# clock_v2.net
KiCad netlist of a schematic drawn in EAGLE
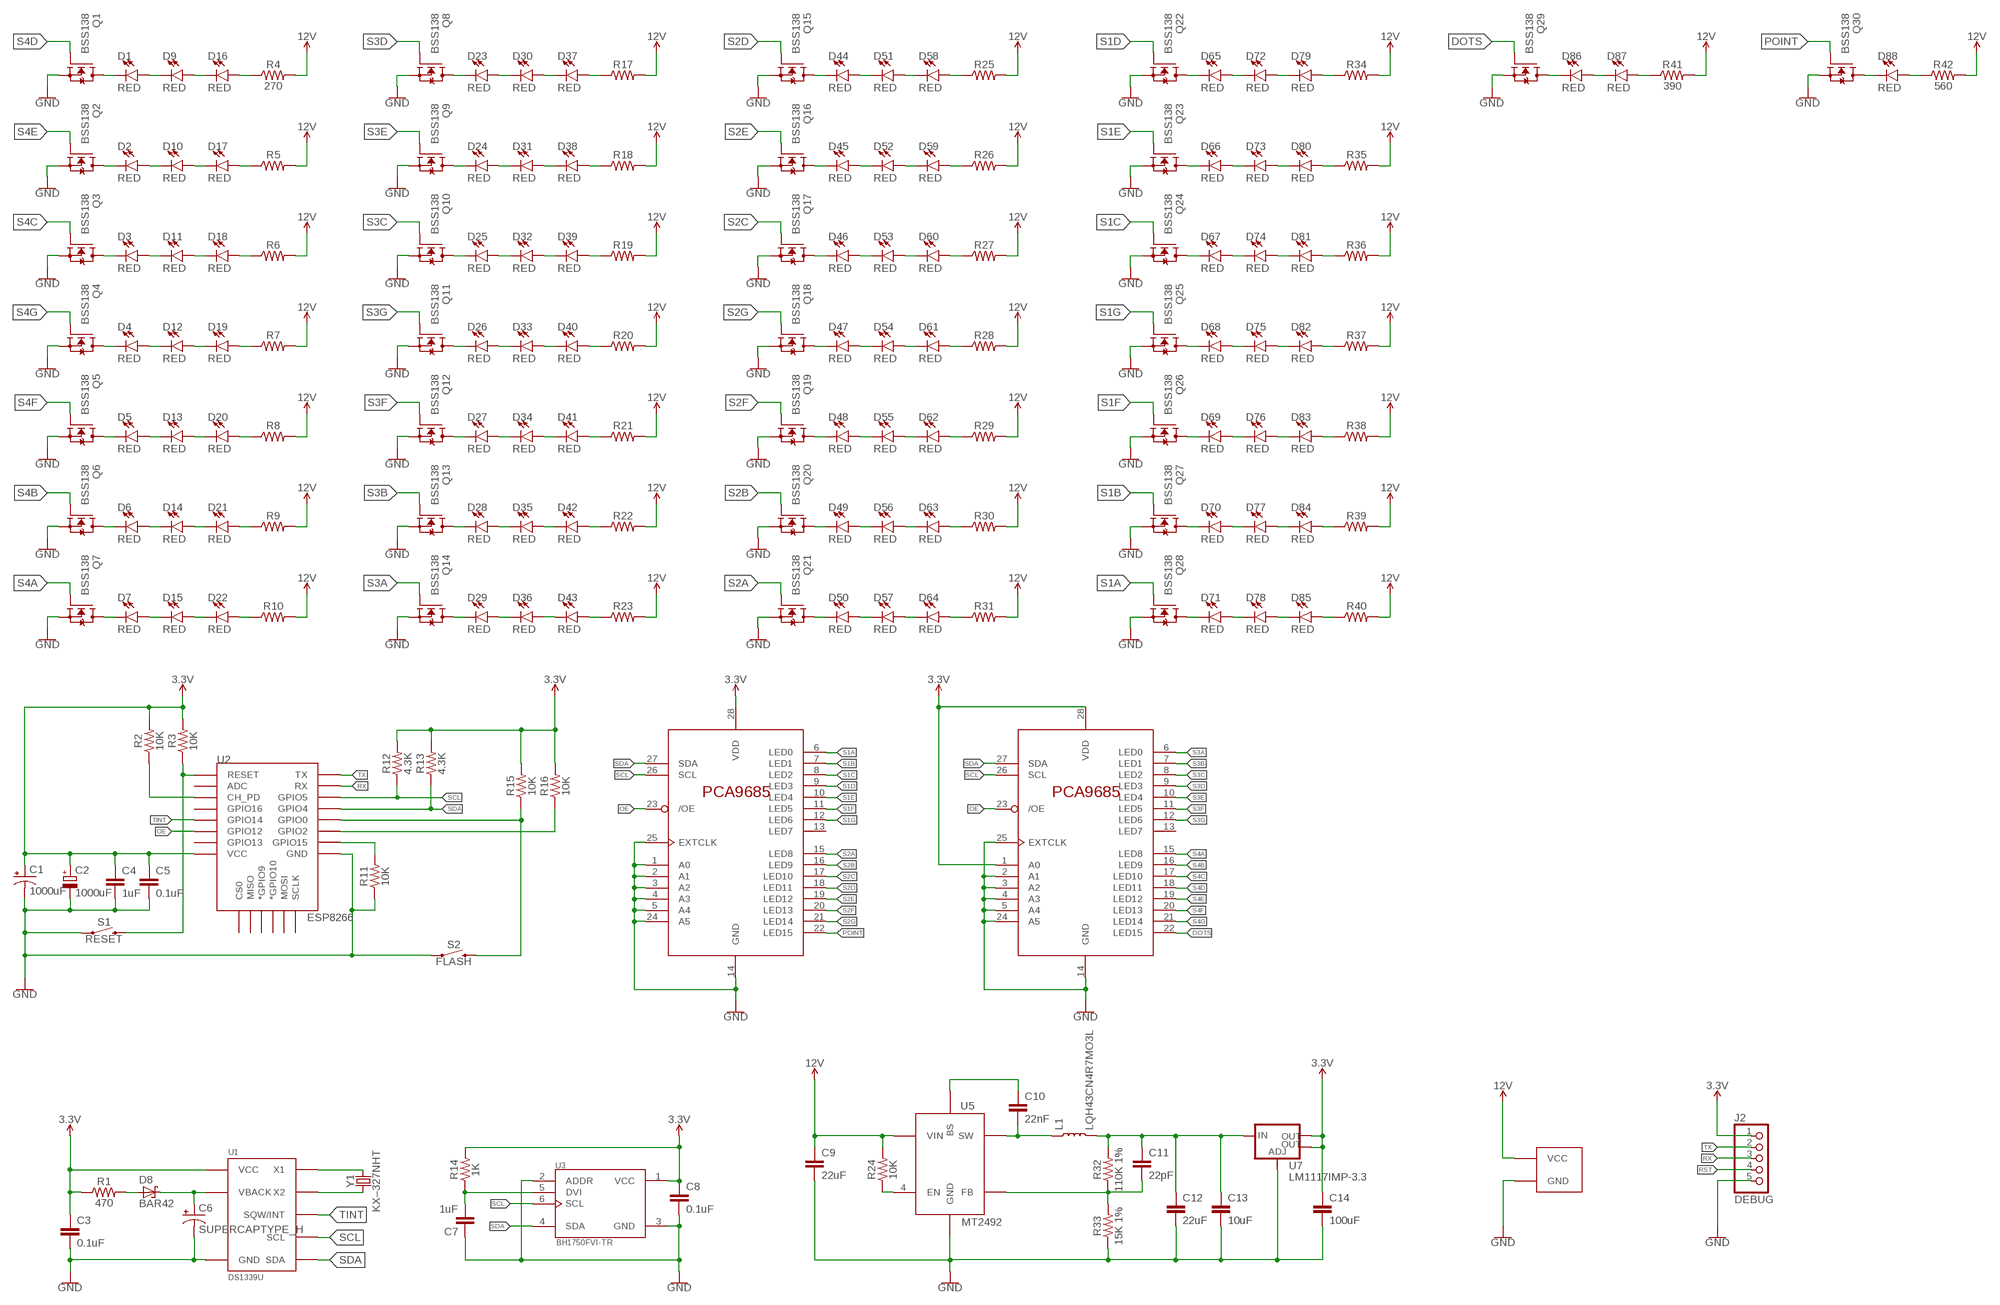
[diagram p0: schematic, sheet 1]

(export (version "E")
  (design (tool "Eeschema 10.0.6"))
  (components
    (comp (ref "C1")
      (value "1000uF")
      (footprint "eagle-import:CAP_8X11.5_P-3.5")
      (libsource (lib "eagle-import") (part "CAP-RADIAL-8MM"))
    )
    (comp (ref "C2")
      (value "1000uF")
      (footprint "eagle-import:D_7343-31R")
      (libsource (lib "eagle-import") (part "CPOL-EUD/7343-31R"))
    )
    (comp (ref "C3")
      (value "0.1uF")
      (footprint "eagle-import:1206")
      (libsource (lib "eagle-import") (part "1.0UF-1206-50V-10%"))
    )
    (comp (ref "C4")
      (value "1uF")
      (footprint "eagle-import:1206")
      (libsource (lib "eagle-import") (part "1.0UF-1206-50V-10%"))
    )
    (comp (ref "C5")
      (value "0.1uF")
      (footprint "eagle-import:1206")
      (libsource (lib "eagle-import") (part "1.0UF-1206-50V-10%"))
    )
    (comp (ref "C6")
      (value "SUPERCAPTYPE_H")
      (footprint "eagle-import:IONISTOR_TYPE_H")
      (libsource (lib "eagle-import") (part "SUPERCAPTYPE_H"))
    )
    (comp (ref "C7")
      (value "1uF")
      (footprint "eagle-import:1206")
      (libsource (lib "eagle-import") (part "1.0UF-1206-50V-10%"))
    )
    (comp (ref "C8")
      (value "0.1uF")
      (footprint "eagle-import:1206")
      (libsource (lib "eagle-import") (part "1.0UF-1206-50V-10%"))
    )
    (comp (ref "C9")
      (value "22uF")
      (footprint "eagle-import:1206")
      (libsource (lib "eagle-import") (part "1.0UF-1206-50V-10%"))
    )
    (comp (ref "C10")
      (value "22nF")
      (footprint "eagle-import:1206")
      (libsource (lib "eagle-import") (part "1.0UF-1206-50V-10%"))
    )
    (comp (ref "C11")
      (value "22pF")
      (footprint "eagle-import:1206")
      (libsource (lib "eagle-import") (part "1.0UF-1206-50V-10%"))
    )
    (comp (ref "C12")
      (value "22uF")
      (footprint "eagle-import:1206")
      (libsource (lib "eagle-import") (part "1.0UF-1206-50V-10%"))
    )
    (comp (ref "C13")
      (value "10uF")
      (footprint "eagle-import:1206")
      (libsource (lib "eagle-import") (part "1.0UF-1206-50V-10%"))
    )
    (comp (ref "C14")
      (value "100uF")
      (footprint "eagle-import:C_6032-28R")
      (libsource (lib "eagle-import") (part "CAP_TANTALUM_C"))
    )
    (comp (ref "D1")
      (value "RED")
      (footprint "eagle-import:LED-1206")
      (libsource (lib "eagle-import") (part "LED-RED1206"))
    )
    (comp (ref "D2")
      (value "RED")
      (footprint "eagle-import:LED-1206")
      (libsource (lib "eagle-import") (part "LED-RED1206"))
    )
    (comp (ref "D3")
      (value "RED")
      (footprint "eagle-import:LED-1206")
      (libsource (lib "eagle-import") (part "LED-RED1206"))
    )
    (comp (ref "D4")
      (value "RED")
      (footprint "eagle-import:LED-1206")
      (libsource (lib "eagle-import") (part "LED-RED1206"))
    )
    (comp (ref "D5")
      (value "RED")
      (footprint "eagle-import:LED-1206")
      (libsource (lib "eagle-import") (part "LED-RED1206"))
    )
    (comp (ref "D6")
      (value "RED")
      (footprint "eagle-import:LED-1206")
      (libsource (lib "eagle-import") (part "LED-RED1206"))
    )
    (comp (ref "D7")
      (value "RED")
      (footprint "eagle-import:LED-1206")
      (libsource (lib "eagle-import") (part "LED-RED1206"))
    )
    (comp (ref "D8")
      (value "BAR42")
      (footprint "eagle-import:SOT23")
      (libsource (lib "eagle-import") (part "BAR42"))
    )
    (comp (ref "D9")
      (value "RED")
      (footprint "eagle-import:LED-1206")
      (libsource (lib "eagle-import") (part "LED-RED1206"))
    )
    (comp (ref "D10")
      (value "RED")
      (footprint "eagle-import:LED-1206")
      (libsource (lib "eagle-import") (part "LED-RED1206"))
    )
    (comp (ref "D11")
      (value "RED")
      (footprint "eagle-import:LED-1206")
      (libsource (lib "eagle-import") (part "LED-RED1206"))
    )
    (comp (ref "D12")
      (value "RED")
      (footprint "eagle-import:LED-1206")
      (libsource (lib "eagle-import") (part "LED-RED1206"))
    )
    (comp (ref "D13")
      (value "RED")
      (footprint "eagle-import:LED-1206")
      (libsource (lib "eagle-import") (part "LED-RED1206"))
    )
    (comp (ref "D14")
      (value "RED")
      (footprint "eagle-import:LED-1206")
      (libsource (lib "eagle-import") (part "LED-RED1206"))
    )
    (comp (ref "D15")
      (value "RED")
      (footprint "eagle-import:LED-1206")
      (libsource (lib "eagle-import") (part "LED-RED1206"))
    )
    (comp (ref "D16")
      (value "RED")
      (footprint "eagle-import:LED-1206")
      (libsource (lib "eagle-import") (part "LED-RED1206"))
    )
    (comp (ref "D17")
      (value "RED")
      (footprint "eagle-import:LED-1206")
      (libsource (lib "eagle-import") (part "LED-RED1206"))
    )
    (comp (ref "D18")
      (value "RED")
      (footprint "eagle-import:LED-1206")
      (libsource (lib "eagle-import") (part "LED-RED1206"))
    )
    (comp (ref "D19")
      (value "RED")
      (footprint "eagle-import:LED-1206")
      (libsource (lib "eagle-import") (part "LED-RED1206"))
    )
    (comp (ref "D20")
      (value "RED")
      (footprint "eagle-import:LED-1206")
      (libsource (lib "eagle-import") (part "LED-RED1206"))
    )
    (comp (ref "D21")
      (value "RED")
      (footprint "eagle-import:LED-1206")
      (libsource (lib "eagle-import") (part "LED-RED1206"))
    )
    (comp (ref "D22")
      (value "RED")
      (footprint "eagle-import:LED-1206")
      (libsource (lib "eagle-import") (part "LED-RED1206"))
    )
    (comp (ref "D23")
      (value "RED")
      (footprint "eagle-import:LED-1206")
      (libsource (lib "eagle-import") (part "LED-RED1206"))
    )
    (comp (ref "D24")
      (value "RED")
      (footprint "eagle-import:LED-1206")
      (libsource (lib "eagle-import") (part "LED-RED1206"))
    )
    (comp (ref "D25")
      (value "RED")
      (footprint "eagle-import:LED-1206")
      (libsource (lib "eagle-import") (part "LED-RED1206"))
    )
    (comp (ref "D26")
      (value "RED")
      (footprint "eagle-import:LED-1206")
      (libsource (lib "eagle-import") (part "LED-RED1206"))
    )
    (comp (ref "D27")
      (value "RED")
      (footprint "eagle-import:LED-1206")
      (libsource (lib "eagle-import") (part "LED-RED1206"))
    )
    (comp (ref "D28")
      (value "RED")
      (footprint "eagle-import:LED-1206")
      (libsource (lib "eagle-import") (part "LED-RED1206"))
    )
    (comp (ref "D29")
      (value "RED")
      (footprint "eagle-import:LED-1206")
      (libsource (lib "eagle-import") (part "LED-RED1206"))
    )
    (comp (ref "D30")
      (value "RED")
      (footprint "eagle-import:LED-1206")
      (libsource (lib "eagle-import") (part "LED-RED1206"))
    )
    (comp (ref "D31")
      (value "RED")
      (footprint "eagle-import:LED-1206")
      (libsource (lib "eagle-import") (part "LED-RED1206"))
    )
    (comp (ref "D32")
      (value "RED")
      (footprint "eagle-import:LED-1206")
      (libsource (lib "eagle-import") (part "LED-RED1206"))
    )
    (comp (ref "D33")
      (value "RED")
      (footprint "eagle-import:LED-1206")
      (libsource (lib "eagle-import") (part "LED-RED1206"))
    )
    (comp (ref "D34")
      (value "RED")
      (footprint "eagle-import:LED-1206")
      (libsource (lib "eagle-import") (part "LED-RED1206"))
    )
    (comp (ref "D35")
      (value "RED")
      (footprint "eagle-import:LED-1206")
      (libsource (lib "eagle-import") (part "LED-RED1206"))
    )
    (comp (ref "D36")
      (value "RED")
      (footprint "eagle-import:LED-1206")
      (libsource (lib "eagle-import") (part "LED-RED1206"))
    )
    (comp (ref "D37")
      (value "RED")
      (footprint "eagle-import:LED-1206")
      (libsource (lib "eagle-import") (part "LED-RED1206"))
    )
    (comp (ref "D38")
      (value "RED")
      (footprint "eagle-import:LED-1206")
      (libsource (lib "eagle-import") (part "LED-RED1206"))
    )
    (comp (ref "D39")
      (value "RED")
      (footprint "eagle-import:LED-1206")
      (libsource (lib "eagle-import") (part "LED-RED1206"))
    )
    (comp (ref "D40")
      (value "RED")
      (footprint "eagle-import:LED-1206")
      (libsource (lib "eagle-import") (part "LED-RED1206"))
    )
    (comp (ref "D41")
      (value "RED")
      (footprint "eagle-import:LED-1206")
      (libsource (lib "eagle-import") (part "LED-RED1206"))
    )
    (comp (ref "D42")
      (value "RED")
      (footprint "eagle-import:LED-1206")
      (libsource (lib "eagle-import") (part "LED-RED1206"))
    )
    (comp (ref "D43")
      (value "RED")
      (footprint "eagle-import:LED-1206")
      (libsource (lib "eagle-import") (part "LED-RED1206"))
    )
    (comp (ref "D44")
      (value "RED")
      (footprint "eagle-import:LED-1206")
      (libsource (lib "eagle-import") (part "LED-RED1206"))
    )
    (comp (ref "D45")
      (value "RED")
      (footprint "eagle-import:LED-1206")
      (libsource (lib "eagle-import") (part "LED-RED1206"))
    )
    (comp (ref "D46")
      (value "RED")
      (footprint "eagle-import:LED-1206")
      (libsource (lib "eagle-import") (part "LED-RED1206"))
    )
    (comp (ref "D47")
      (value "RED")
      (footprint "eagle-import:LED-1206")
      (libsource (lib "eagle-import") (part "LED-RED1206"))
    )
    (comp (ref "D48")
      (value "RED")
      (footprint "eagle-import:LED-1206")
      (libsource (lib "eagle-import") (part "LED-RED1206"))
    )
    (comp (ref "D49")
      (value "RED")
      (footprint "eagle-import:LED-1206")
      (libsource (lib "eagle-import") (part "LED-RED1206"))
    )
    (comp (ref "D50")
      (value "RED")
      (footprint "eagle-import:LED-1206")
      (libsource (lib "eagle-import") (part "LED-RED1206"))
    )
    (comp (ref "D51")
      (value "RED")
      (footprint "eagle-import:LED-1206")
      (libsource (lib "eagle-import") (part "LED-RED1206"))
    )
    (comp (ref "D52")
      (value "RED")
      (footprint "eagle-import:LED-1206")
      (libsource (lib "eagle-import") (part "LED-RED1206"))
    )
    (comp (ref "D53")
      (value "RED")
      (footprint "eagle-import:LED-1206")
      (libsource (lib "eagle-import") (part "LED-RED1206"))
    )
    (comp (ref "D54")
      (value "RED")
      (footprint "eagle-import:LED-1206")
      (libsource (lib "eagle-import") (part "LED-RED1206"))
    )
    (comp (ref "D55")
      (value "RED")
      (footprint "eagle-import:LED-1206")
      (libsource (lib "eagle-import") (part "LED-RED1206"))
    )
    (comp (ref "D56")
      (value "RED")
      (footprint "eagle-import:LED-1206")
      (libsource (lib "eagle-import") (part "LED-RED1206"))
    )
    (comp (ref "D57")
      (value "RED")
      (footprint "eagle-import:LED-1206")
      (libsource (lib "eagle-import") (part "LED-RED1206"))
    )
    (comp (ref "D58")
      (value "RED")
      (footprint "eagle-import:LED-1206")
      (libsource (lib "eagle-import") (part "LED-RED1206"))
    )
    (comp (ref "D59")
      (value "RED")
      (footprint "eagle-import:LED-1206")
      (libsource (lib "eagle-import") (part "LED-RED1206"))
    )
    (comp (ref "D60")
      (value "RED")
      (footprint "eagle-import:LED-1206")
      (libsource (lib "eagle-import") (part "LED-RED1206"))
    )
    (comp (ref "D61")
      (value "RED")
      (footprint "eagle-import:LED-1206")
      (libsource (lib "eagle-import") (part "LED-RED1206"))
    )
    (comp (ref "D62")
      (value "RED")
      (footprint "eagle-import:LED-1206")
      (libsource (lib "eagle-import") (part "LED-RED1206"))
    )
    (comp (ref "D63")
      (value "RED")
      (footprint "eagle-import:LED-1206")
      (libsource (lib "eagle-import") (part "LED-RED1206"))
    )
    (comp (ref "D64")
      (value "RED")
      (footprint "eagle-import:LED-1206")
      (libsource (lib "eagle-import") (part "LED-RED1206"))
    )
    (comp (ref "D65")
      (value "RED")
      (footprint "eagle-import:LED-1206")
      (libsource (lib "eagle-import") (part "LED-RED1206"))
    )
    (comp (ref "D66")
      (value "RED")
      (footprint "eagle-import:LED-1206")
      (libsource (lib "eagle-import") (part "LED-RED1206"))
    )
    (comp (ref "D67")
      (value "RED")
      (footprint "eagle-import:LED-1206")
      (libsource (lib "eagle-import") (part "LED-RED1206"))
    )
    (comp (ref "D68")
      (value "RED")
      (footprint "eagle-import:LED-1206")
      (libsource (lib "eagle-import") (part "LED-RED1206"))
    )
    (comp (ref "D69")
      (value "RED")
      (footprint "eagle-import:LED-1206")
      (libsource (lib "eagle-import") (part "LED-RED1206"))
    )
    (comp (ref "D70")
      (value "RED")
      (footprint "eagle-import:LED-1206")
      (libsource (lib "eagle-import") (part "LED-RED1206"))
    )
    (comp (ref "D71")
      (value "RED")
      (footprint "eagle-import:LED-1206")
      (libsource (lib "eagle-import") (part "LED-RED1206"))
    )
    (comp (ref "D72")
      (value "RED")
      (footprint "eagle-import:LED-1206")
      (libsource (lib "eagle-import") (part "LED-RED1206"))
    )
    (comp (ref "D73")
      (value "RED")
      (footprint "eagle-import:LED-1206")
      (libsource (lib "eagle-import") (part "LED-RED1206"))
    )
    (comp (ref "D74")
      (value "RED")
      (footprint "eagle-import:LED-1206")
      (libsource (lib "eagle-import") (part "LED-RED1206"))
    )
    (comp (ref "D75")
      (value "RED")
      (footprint "eagle-import:LED-1206")
      (libsource (lib "eagle-import") (part "LED-RED1206"))
    )
    (comp (ref "D76")
      (value "RED")
      (footprint "eagle-import:LED-1206")
      (libsource (lib "eagle-import") (part "LED-RED1206"))
    )
    (comp (ref "D77")
      (value "RED")
      (footprint "eagle-import:LED-1206")
      (libsource (lib "eagle-import") (part "LED-RED1206"))
    )
    (comp (ref "D78")
      (value "RED")
      (footprint "eagle-import:LED-1206")
      (libsource (lib "eagle-import") (part "LED-RED1206"))
    )
    (comp (ref "D79")
      (value "RED")
      (footprint "eagle-import:LED-1206")
      (libsource (lib "eagle-import") (part "LED-RED1206"))
    )
    (comp (ref "D80")
      (value "RED")
      (footprint "eagle-import:LED-1206")
      (libsource (lib "eagle-import") (part "LED-RED1206"))
    )
    (comp (ref "D81")
      (value "RED")
      (footprint "eagle-import:LED-1206")
      (libsource (lib "eagle-import") (part "LED-RED1206"))
    )
    (comp (ref "D82")
      (value "RED")
      (footprint "eagle-import:LED-1206")
      (libsource (lib "eagle-import") (part "LED-RED1206"))
    )
    (comp (ref "D83")
      (value "RED")
      (footprint "eagle-import:LED-1206")
      (libsource (lib "eagle-import") (part "LED-RED1206"))
    )
    (comp (ref "D84")
      (value "RED")
      (footprint "eagle-import:LED-1206")
      (libsource (lib "eagle-import") (part "LED-RED1206"))
    )
    (comp (ref "D85")
      (value "RED")
      (footprint "eagle-import:LED-1206")
      (libsource (lib "eagle-import") (part "LED-RED1206"))
    )
    (comp (ref "D86")
      (value "RED")
      (footprint "eagle-import:LED-1206")
      (libsource (lib "eagle-import") (part "LED-RED1206"))
    )
    (comp (ref "D87")
      (value "RED")
      (footprint "eagle-import:LED-1206")
      (libsource (lib "eagle-import") (part "LED-RED1206"))
    )
    (comp (ref "D88")
      (value "RED")
      (footprint "eagle-import:LED-1206")
      (libsource (lib "eagle-import") (part "LED-RED1206"))
    )
    (comp (ref "J1")
      (value "POWER_SMD5.08")
      (footprint "eagle-import:POWER_SMD_5.08")
      (libsource (lib "eagle-import") (part "POWER_SMD5.08"))
    )
    (comp (ref "J2")
      (value "DEBUG")
      (footprint "eagle-import:ESP8266_DEBUG")
      (libsource (lib "eagle-import") (part "ESP8266_DEBUG"))
    )
    (comp (ref "L1")
      (value "LQH43CN4R7MO3L")
      (footprint "eagle-import:C1812")
      (libsource (lib "eagle-import") (part "INDUCTOR_SMD_1812"))
    )
    (comp (ref "Q1")
      (value "BSS138")
      (footprint "eagle-import:SOT23")
      (fields (field (name "MF") "Fairchild"))
      (libsource (lib "eagle-import") (part "BSS138"))
    )
    (comp (ref "Q2")
      (value "BSS138")
      (footprint "eagle-import:SOT23")
      (fields (field (name "MF") "Fairchild"))
      (libsource (lib "eagle-import") (part "BSS138"))
    )
    (comp (ref "Q3")
      (value "BSS138")
      (footprint "eagle-import:SOT23")
      (fields (field (name "MF") "Fairchild"))
      (libsource (lib "eagle-import") (part "BSS138"))
    )
    (comp (ref "Q4")
      (value "BSS138")
      (footprint "eagle-import:SOT23")
      (fields (field (name "MF") "Fairchild"))
      (libsource (lib "eagle-import") (part "BSS138"))
    )
    (comp (ref "Q5")
      (value "BSS138")
      (footprint "eagle-import:SOT23")
      (fields (field (name "MF") "Fairchild"))
      (libsource (lib "eagle-import") (part "BSS138"))
    )
    (comp (ref "Q6")
      (value "BSS138")
      (footprint "eagle-import:SOT23")
      (fields (field (name "MF") "Fairchild"))
      (libsource (lib "eagle-import") (part "BSS138"))
    )
    (comp (ref "Q7")
      (value "BSS138")
      (footprint "eagle-import:SOT23")
      (fields (field (name "MF") "Fairchild"))
      (libsource (lib "eagle-import") (part "BSS138"))
    )
    (comp (ref "Q8")
      (value "BSS138")
      (footprint "eagle-import:SOT23")
      (fields (field (name "MF") "Fairchild"))
      (libsource (lib "eagle-import") (part "BSS138"))
    )
    (comp (ref "Q9")
      (value "BSS138")
      (footprint "eagle-import:SOT23")
      (fields (field (name "MF") "Fairchild"))
      (libsource (lib "eagle-import") (part "BSS138"))
    )
    (comp (ref "Q10")
      (value "BSS138")
      (footprint "eagle-import:SOT23")
      (fields (field (name "MF") "Fairchild"))
      (libsource (lib "eagle-import") (part "BSS138"))
    )
    (comp (ref "Q11")
      (value "BSS138")
      (footprint "eagle-import:SOT23")
      (fields (field (name "MF") "Fairchild"))
      (libsource (lib "eagle-import") (part "BSS138"))
    )
    (comp (ref "Q12")
      (value "BSS138")
      (footprint "eagle-import:SOT23")
      (fields (field (name "MF") "Fairchild"))
      (libsource (lib "eagle-import") (part "BSS138"))
    )
    (comp (ref "Q13")
      (value "BSS138")
      (footprint "eagle-import:SOT23")
      (fields (field (name "MF") "Fairchild"))
      (libsource (lib "eagle-import") (part "BSS138"))
    )
    (comp (ref "Q14")
      (value "BSS138")
      (footprint "eagle-import:SOT23")
      (fields (field (name "MF") "Fairchild"))
      (libsource (lib "eagle-import") (part "BSS138"))
    )
    (comp (ref "Q15")
      (value "BSS138")
      (footprint "eagle-import:SOT23")
      (fields (field (name "MF") "Fairchild"))
      (libsource (lib "eagle-import") (part "BSS138"))
    )
    (comp (ref "Q16")
      (value "BSS138")
      (footprint "eagle-import:SOT23")
      (fields (field (name "MF") "Fairchild"))
      (libsource (lib "eagle-import") (part "BSS138"))
    )
    (comp (ref "Q17")
      (value "BSS138")
      (footprint "eagle-import:SOT23")
      (fields (field (name "MF") "Fairchild"))
      (libsource (lib "eagle-import") (part "BSS138"))
    )
    (comp (ref "Q18")
      (value "BSS138")
      (footprint "eagle-import:SOT23")
      (fields (field (name "MF") "Fairchild"))
      (libsource (lib "eagle-import") (part "BSS138"))
    )
    (comp (ref "Q19")
      (value "BSS138")
      (footprint "eagle-import:SOT23")
      (fields (field (name "MF") "Fairchild"))
      (libsource (lib "eagle-import") (part "BSS138"))
    )
    (comp (ref "Q20")
      (value "BSS138")
      (footprint "eagle-import:SOT23")
      (fields (field (name "MF") "Fairchild"))
      (libsource (lib "eagle-import") (part "BSS138"))
    )
    (comp (ref "Q21")
      (value "BSS138")
      (footprint "eagle-import:SOT23")
      (fields (field (name "MF") "Fairchild"))
      (libsource (lib "eagle-import") (part "BSS138"))
    )
    (comp (ref "Q22")
      (value "BSS138")
      (footprint "eagle-import:SOT23")
      (fields (field (name "MF") "Fairchild"))
      (libsource (lib "eagle-import") (part "BSS138"))
    )
    (comp (ref "Q23")
      (value "BSS138")
      (footprint "eagle-import:SOT23")
      (fields (field (name "MF") "Fairchild"))
      (libsource (lib "eagle-import") (part "BSS138"))
    )
    (comp (ref "Q24")
      (value "BSS138")
      (footprint "eagle-import:SOT23")
      (fields (field (name "MF") "Fairchild"))
      (libsource (lib "eagle-import") (part "BSS138"))
    )
    (comp (ref "Q25")
      (value "BSS138")
      (footprint "eagle-import:SOT23")
      (fields (field (name "MF") "Fairchild"))
      (libsource (lib "eagle-import") (part "BSS138"))
    )
    (comp (ref "Q26")
      (value "BSS138")
      (footprint "eagle-import:SOT23")
      (fields (field (name "MF") "Fairchild"))
      (libsource (lib "eagle-import") (part "BSS138"))
    )
    (comp (ref "Q27")
      (value "BSS138")
      (footprint "eagle-import:SOT23")
      (fields (field (name "MF") "Fairchild"))
      (libsource (lib "eagle-import") (part "BSS138"))
    )
    (comp (ref "Q28")
      (value "BSS138")
      (footprint "eagle-import:SOT23")
      (fields (field (name "MF") "Fairchild"))
      (libsource (lib "eagle-import") (part "BSS138"))
    )
    (comp (ref "Q29")
      (value "BSS138")
      (footprint "eagle-import:SOT23")
      (fields (field (name "MF") "Fairchild"))
      (libsource (lib "eagle-import") (part "BSS138"))
    )
    (comp (ref "Q30")
      (value "BSS138")
      (footprint "eagle-import:SOT23")
      (fields (field (name "MF") "Fairchild"))
      (libsource (lib "eagle-import") (part "BSS138"))
    )
    (comp (ref "R1")
      (value "470")
      (footprint "eagle-import:1206")
      (libsource (lib "eagle-import") (part "RESISTOR1206"))
    )
    (comp (ref "R2")
      (value "10K")
      (footprint "eagle-import:1206")
      (libsource (lib "eagle-import") (part "RESISTOR1206"))
    )
    (comp (ref "R3")
      (value "10K")
      (footprint "eagle-import:1206")
      (libsource (lib "eagle-import") (part "RESISTOR1206"))
    )
    (comp (ref "R4")
      (value "270")
      (footprint "eagle-import:1206")
      (libsource (lib "eagle-import") (part "RESISTOR1206"))
    )
    (comp (ref "R5")
      (value "RESISTOR1206")
      (footprint "eagle-import:1206")
      (libsource (lib "eagle-import") (part "RESISTOR1206"))
    )
    (comp (ref "R6")
      (value "RESISTOR1206")
      (footprint "eagle-import:1206")
      (libsource (lib "eagle-import") (part "RESISTOR1206"))
    )
    (comp (ref "R7")
      (value "RESISTOR1206")
      (footprint "eagle-import:1206")
      (libsource (lib "eagle-import") (part "RESISTOR1206"))
    )
    (comp (ref "R8")
      (value "RESISTOR1206")
      (footprint "eagle-import:1206")
      (libsource (lib "eagle-import") (part "RESISTOR1206"))
    )
    (comp (ref "R9")
      (value "RESISTOR1206")
      (footprint "eagle-import:1206")
      (libsource (lib "eagle-import") (part "RESISTOR1206"))
    )
    (comp (ref "R10")
      (value "RESISTOR1206")
      (footprint "eagle-import:1206")
      (libsource (lib "eagle-import") (part "RESISTOR1206"))
    )
    (comp (ref "R11")
      (value "10K")
      (footprint "eagle-import:1206")
      (libsource (lib "eagle-import") (part "RESISTOR1206"))
    )
    (comp (ref "R12")
      (value "4.3K")
      (footprint "eagle-import:1206")
      (libsource (lib "eagle-import") (part "RESISTOR1206"))
    )
    (comp (ref "R13")
      (value "4.3K")
      (footprint "eagle-import:1206")
      (libsource (lib "eagle-import") (part "RESISTOR1206"))
    )
    (comp (ref "R14")
      (value "1K")
      (footprint "eagle-import:1206")
      (libsource (lib "eagle-import") (part "RESISTOR1206"))
    )
    (comp (ref "R15")
      (value "10K")
      (footprint "eagle-import:1206")
      (libsource (lib "eagle-import") (part "RESISTOR1206"))
    )
    (comp (ref "R16")
      (value "10K")
      (footprint "eagle-import:1206")
      (libsource (lib "eagle-import") (part "RESISTOR1206"))
    )
    (comp (ref "R17")
      (value "RESISTOR1206")
      (footprint "eagle-import:1206")
      (libsource (lib "eagle-import") (part "RESISTOR1206"))
    )
    (comp (ref "R18")
      (value "RESISTOR1206")
      (footprint "eagle-import:1206")
      (libsource (lib "eagle-import") (part "RESISTOR1206"))
    )
    (comp (ref "R19")
      (value "RESISTOR1206")
      (footprint "eagle-import:1206")
      (libsource (lib "eagle-import") (part "RESISTOR1206"))
    )
    (comp (ref "R20")
      (value "RESISTOR1206")
      (footprint "eagle-import:1206")
      (libsource (lib "eagle-import") (part "RESISTOR1206"))
    )
    (comp (ref "R21")
      (value "RESISTOR1206")
      (footprint "eagle-import:1206")
      (libsource (lib "eagle-import") (part "RESISTOR1206"))
    )
    (comp (ref "R22")
      (value "RESISTOR1206")
      (footprint "eagle-import:1206")
      (libsource (lib "eagle-import") (part "RESISTOR1206"))
    )
    (comp (ref "R23")
      (value "RESISTOR1206")
      (footprint "eagle-import:1206")
      (libsource (lib "eagle-import") (part "RESISTOR1206"))
    )
    (comp (ref "R24")
      (value "10K")
      (footprint "eagle-import:1206")
      (libsource (lib "eagle-import") (part "RESISTOR1206"))
    )
    (comp (ref "R25")
      (value "RESISTOR1206")
      (footprint "eagle-import:1206")
      (libsource (lib "eagle-import") (part "RESISTOR1206"))
    )
    (comp (ref "R26")
      (value "RESISTOR1206")
      (footprint "eagle-import:1206")
      (libsource (lib "eagle-import") (part "RESISTOR1206"))
    )
    (comp (ref "R27")
      (value "RESISTOR1206")
      (footprint "eagle-import:1206")
      (libsource (lib "eagle-import") (part "RESISTOR1206"))
    )
    (comp (ref "R28")
      (value "RESISTOR1206")
      (footprint "eagle-import:1206")
      (libsource (lib "eagle-import") (part "RESISTOR1206"))
    )
    (comp (ref "R29")
      (value "RESISTOR1206")
      (footprint "eagle-import:1206")
      (libsource (lib "eagle-import") (part "RESISTOR1206"))
    )
    (comp (ref "R30")
      (value "RESISTOR1206")
      (footprint "eagle-import:1206")
      (libsource (lib "eagle-import") (part "RESISTOR1206"))
    )
    (comp (ref "R31")
      (value "RESISTOR1206")
      (footprint "eagle-import:1206")
      (libsource (lib "eagle-import") (part "RESISTOR1206"))
    )
    (comp (ref "R32")
      (value "110K 1%")
      (footprint "eagle-import:1206")
      (libsource (lib "eagle-import") (part "RESISTOR1206"))
    )
    (comp (ref "R33")
      (value "15K 1%")
      (footprint "eagle-import:1206")
      (libsource (lib "eagle-import") (part "RESISTOR1206"))
    )
    (comp (ref "R34")
      (value "RESISTOR1206")
      (footprint "eagle-import:1206")
      (libsource (lib "eagle-import") (part "RESISTOR1206"))
    )
    (comp (ref "R35")
      (value "RESISTOR1206")
      (footprint "eagle-import:1206")
      (libsource (lib "eagle-import") (part "RESISTOR1206"))
    )
    (comp (ref "R36")
      (value "RESISTOR1206")
      (footprint "eagle-import:1206")
      (libsource (lib "eagle-import") (part "RESISTOR1206"))
    )
    (comp (ref "R37")
      (value "RESISTOR1206")
      (footprint "eagle-import:1206")
      (libsource (lib "eagle-import") (part "RESISTOR1206"))
    )
    (comp (ref "R38")
      (value "RESISTOR1206")
      (footprint "eagle-import:1206")
      (libsource (lib "eagle-import") (part "RESISTOR1206"))
    )
    (comp (ref "R39")
      (value "RESISTOR1206")
      (footprint "eagle-import:1206")
      (libsource (lib "eagle-import") (part "RESISTOR1206"))
    )
    (comp (ref "R40")
      (value "RESISTOR1206")
      (footprint "eagle-import:1206")
      (libsource (lib "eagle-import") (part "RESISTOR1206"))
    )
    (comp (ref "R41")
      (value "390")
      (footprint "eagle-import:1206")
      (libsource (lib "eagle-import") (part "RESISTOR1206"))
    )
    (comp (ref "R42")
      (value "560")
      (footprint "eagle-import:1206")
      (libsource (lib "eagle-import") (part "RESISTOR1206"))
    )
    (comp (ref "S1")
      (value "RESET")
      (footprint "eagle-import:TACTILE_SWITCH_SMD_5.2MM")
      (libsource (lib "eagle-import") (part "MOMENTARY-SWITCH-SPST-SMD-5.2-REDUNDANT"))
    )
    (comp (ref "S2")
      (value "FLASH")
      (footprint "eagle-import:TACTILE_SWITCH_SMD_5.2MM")
      (libsource (lib "eagle-import") (part "MOMENTARY-SWITCH-SPST-SMD-5.2-REDUNDANT"))
    )
    (comp (ref "U1")
      (value "DS1339U")
      (footprint "eagle-import:DS1339U")
      (libsource (lib "eagle-import") (part "DS1339U"))
    )
    (comp (ref "U2")
      (value "ESP8266")
      (footprint "eagle-import:ESP12E-SMD")
      (libsource (lib "eagle-import") (part "ESP12ESMD"))
    )
    (comp (ref "U3")
      (value "BH1750FVI-TR")
      (footprint "eagle-import:SOTFL50P300X75-6N")
      (fields (field (name "MF") "Rohm"))
      (libsource (lib "eagle-import") (part "BH1750FVI-TR"))
    )
    (comp (ref "U4")
      (value "PCA9685PW")
      (footprint "eagle-import:TSSOP28")
      (libsource (lib "eagle-import") (part "PCA9685PW"))
    )
    (comp (ref "U5")
      (value "MT2492")
      (footprint "eagle-import:SOT23-6")
      (libsource (lib "eagle-import") (part "MT2492"))
    )
    (comp (ref "U6")
      (value "PCA9685PW")
      (footprint "eagle-import:TSSOP28")
      (libsource (lib "eagle-import") (part "PCA9685PW"))
    )
    (comp (ref "U7")
      (value "LM1117IMP-3.3")
      (footprint "eagle-import:SOT223")
      (libsource (lib "eagle-import") (part "V_REG_LM1117SOT223"))
    )
    (comp (ref "Y1")
      (value "KX–327NHT")
      (footprint "eagle-import:QSMD3.2X1.5")
      (libsource (lib "eagle-import") (part "KX–327NHT"))
    )
  )
  (nets
    (net (code "1") (name "3.3V") (class "Default")
      (node (ref "C1") (pin "+") (pinfunction "+_+") (pintype "passive"))
      (node (ref "C14") (pin "+") (pinfunction "1_+") (pintype "passive"))
      (node (ref "C2") (pin "+") (pinfunction "+_+") (pintype "passive"))
      (node (ref "C3") (pin "1") (pinfunction "1_1") (pintype "passive"))
      (node (ref "C4") (pin "1") (pinfunction "1_1") (pintype "passive"))
      (node (ref "C5") (pin "1") (pinfunction "1_1") (pintype "passive"))
      (node (ref "C8") (pin "1") (pinfunction "1_1") (pintype "passive"))
      (node (ref "J2") (pin "1") (pinfunction "1_1") (pintype "passive"))
      (node (ref "R1") (pin "1") (pinfunction "1_1") (pintype "passive"))
      (node (ref "R12") (pin "2") (pinfunction "2_2") (pintype "passive"))
      (node (ref "R13") (pin "2") (pinfunction "2_2") (pintype "passive"))
      (node (ref "R14") (pin "2") (pinfunction "2_2") (pintype "passive"))
      (node (ref "R15") (pin "2") (pinfunction "2_2") (pintype "passive"))
      (node (ref "R16") (pin "2") (pinfunction "2_2") (pintype "passive"))
      (node (ref "R2") (pin "2") (pinfunction "2_2") (pintype "passive"))
      (node (ref "R3") (pin "2") (pinfunction "2_2") (pintype "passive"))
      (node (ref "U1") (pin "8") (pinfunction "VCC_8") (pintype "power_in"))
      (node (ref "U2") (pin "VCC") (pinfunction "VCC_VCC") (pintype "bidirectional"))
      (node (ref "U3") (pin "1") (pinfunction "VCC_1") (pintype "power_in"))
      (node (ref "U4") (pin "28") (pinfunction "VDD_28") (pintype "power_in"))
      (node (ref "U6") (pin "1") (pinfunction "A0_1") (pintype "bidirectional"))
      (node (ref "U6") (pin "28") (pinfunction "VDD_28") (pintype "power_in"))
      (node (ref "U7") (pin "2") (pinfunction "OUT_2") (pintype "output"))
      (node (ref "U7") (pin "4") (pinfunction "OUT_4") (pintype "output"))
    )
    (net (code "2") (name "12V") (class "Default")
      (node (ref "C9") (pin "1") (pinfunction "1_1") (pintype "passive"))
      (node (ref "J1") (pin "VCC") (pinfunction "VCC_VCC") (pintype "bidirectional"))
      (node (ref "R10") (pin "2") (pinfunction "2_2") (pintype "passive"))
      (node (ref "R17") (pin "2") (pinfunction "2_2") (pintype "passive"))
      (node (ref "R18") (pin "2") (pinfunction "2_2") (pintype "passive"))
      (node (ref "R19") (pin "2") (pinfunction "2_2") (pintype "passive"))
      (node (ref "R20") (pin "2") (pinfunction "2_2") (pintype "passive"))
      (node (ref "R21") (pin "2") (pinfunction "2_2") (pintype "passive"))
      (node (ref "R22") (pin "2") (pinfunction "2_2") (pintype "passive"))
      (node (ref "R23") (pin "2") (pinfunction "2_2") (pintype "passive"))
      (node (ref "R24") (pin "2") (pinfunction "2_2") (pintype "passive"))
      (node (ref "R25") (pin "2") (pinfunction "2_2") (pintype "passive"))
      (node (ref "R26") (pin "2") (pinfunction "2_2") (pintype "passive"))
      (node (ref "R27") (pin "2") (pinfunction "2_2") (pintype "passive"))
      (node (ref "R28") (pin "2") (pinfunction "2_2") (pintype "passive"))
      (node (ref "R29") (pin "2") (pinfunction "2_2") (pintype "passive"))
      (node (ref "R30") (pin "2") (pinfunction "2_2") (pintype "passive"))
      (node (ref "R31") (pin "2") (pinfunction "2_2") (pintype "passive"))
      (node (ref "R34") (pin "2") (pinfunction "2_2") (pintype "passive"))
      (node (ref "R35") (pin "2") (pinfunction "2_2") (pintype "passive"))
      (node (ref "R36") (pin "2") (pinfunction "2_2") (pintype "passive"))
      (node (ref "R37") (pin "2") (pinfunction "2_2") (pintype "passive"))
      (node (ref "R38") (pin "2") (pinfunction "2_2") (pintype "passive"))
      (node (ref "R39") (pin "2") (pinfunction "2_2") (pintype "passive"))
      (node (ref "R4") (pin "2") (pinfunction "2_2") (pintype "passive"))
      (node (ref "R40") (pin "2") (pinfunction "2_2") (pintype "passive"))
      (node (ref "R41") (pin "2") (pinfunction "2_2") (pintype "passive"))
      (node (ref "R42") (pin "2") (pinfunction "2_2") (pintype "passive"))
      (node (ref "R5") (pin "2") (pinfunction "2_2") (pintype "passive"))
      (node (ref "R6") (pin "2") (pinfunction "2_2") (pintype "passive"))
      (node (ref "R7") (pin "2") (pinfunction "2_2") (pintype "passive"))
      (node (ref "R8") (pin "2") (pinfunction "2_2") (pintype "passive"))
      (node (ref "R9") (pin "2") (pinfunction "2_2") (pintype "passive"))
      (node (ref "U5") (pin "5") (pinfunction "VIN_5") (pintype "bidirectional"))
    )
    (net (code "3") (name "DOTS") (class "Default")
      (node (ref "Q29") (pin "1") (pinfunction "G_1") (pintype "passive"))
      (node (ref "U6") (pin "22") (pinfunction "LED15_22") (pintype "bidirectional"))
    )
    (net (code "4") (name "GND") (class "Default")
      (node (ref "C1") (pin "-") (pinfunction "-_-") (pintype "passive"))
      (node (ref "C12") (pin "2") (pinfunction "2_2") (pintype "passive"))
      (node (ref "C13") (pin "2") (pinfunction "2_2") (pintype "passive"))
      (node (ref "C14") (pin "-") (pinfunction "2_-") (pintype "passive"))
      (node (ref "C2") (pin "-") (pinfunction "-_-") (pintype "passive"))
      (node (ref "C3") (pin "2") (pinfunction "2_2") (pintype "passive"))
      (node (ref "C4") (pin "2") (pinfunction "2_2") (pintype "passive"))
      (node (ref "C5") (pin "2") (pinfunction "2_2") (pintype "passive"))
      (node (ref "C6") (pin "GND") (pinfunction "-_GND") (pintype "passive"))
      (node (ref "C7") (pin "1") (pinfunction "1_1") (pintype "passive"))
      (node (ref "C8") (pin "2") (pinfunction "2_2") (pintype "passive"))
      (node (ref "C9") (pin "2") (pinfunction "2_2") (pintype "passive"))
      (node (ref "J1") (pin "GND") (pinfunction "GND_GND") (pintype "bidirectional"))
      (node (ref "J2") (pin "5") (pinfunction "5_5") (pintype "passive"))
      (node (ref "Q1") (pin "2") (pinfunction "S_2") (pintype "passive"))
      (node (ref "Q10") (pin "2") (pinfunction "S_2") (pintype "passive"))
      (node (ref "Q11") (pin "2") (pinfunction "S_2") (pintype "passive"))
      (node (ref "Q12") (pin "2") (pinfunction "S_2") (pintype "passive"))
      (node (ref "Q13") (pin "2") (pinfunction "S_2") (pintype "passive"))
      (node (ref "Q14") (pin "2") (pinfunction "S_2") (pintype "passive"))
      (node (ref "Q15") (pin "2") (pinfunction "S_2") (pintype "passive"))
      (node (ref "Q16") (pin "2") (pinfunction "S_2") (pintype "passive"))
      (node (ref "Q17") (pin "2") (pinfunction "S_2") (pintype "passive"))
      (node (ref "Q18") (pin "2") (pinfunction "S_2") (pintype "passive"))
      (node (ref "Q19") (pin "2") (pinfunction "S_2") (pintype "passive"))
      (node (ref "Q2") (pin "2") (pinfunction "S_2") (pintype "passive"))
      (node (ref "Q20") (pin "2") (pinfunction "S_2") (pintype "passive"))
      (node (ref "Q21") (pin "2") (pinfunction "S_2") (pintype "passive"))
      (node (ref "Q22") (pin "2") (pinfunction "S_2") (pintype "passive"))
      (node (ref "Q23") (pin "2") (pinfunction "S_2") (pintype "passive"))
      (node (ref "Q24") (pin "2") (pinfunction "S_2") (pintype "passive"))
      (node (ref "Q25") (pin "2") (pinfunction "S_2") (pintype "passive"))
      (node (ref "Q26") (pin "2") (pinfunction "S_2") (pintype "passive"))
      (node (ref "Q27") (pin "2") (pinfunction "S_2") (pintype "passive"))
      (node (ref "Q28") (pin "2") (pinfunction "S_2") (pintype "passive"))
      (node (ref "Q29") (pin "2") (pinfunction "S_2") (pintype "passive"))
      (node (ref "Q3") (pin "2") (pinfunction "S_2") (pintype "passive"))
      (node (ref "Q30") (pin "2") (pinfunction "S_2") (pintype "passive"))
      (node (ref "Q4") (pin "2") (pinfunction "S_2") (pintype "passive"))
      (node (ref "Q5") (pin "2") (pinfunction "S_2") (pintype "passive"))
      (node (ref "Q6") (pin "2") (pinfunction "S_2") (pintype "passive"))
      (node (ref "Q7") (pin "2") (pinfunction "S_2") (pintype "passive"))
      (node (ref "Q8") (pin "2") (pinfunction "S_2") (pintype "passive"))
      (node (ref "Q9") (pin "2") (pinfunction "S_2") (pintype "passive"))
      (node (ref "R11") (pin "1") (pinfunction "1_1") (pintype "passive"))
      (node (ref "R33") (pin "1") (pinfunction "1_1") (pintype "passive"))
      (node (ref "S1") (pin "1") (pinfunction "1_1") (pintype "passive"))
      (node (ref "S1") (pin "2") (pinfunction "1_2") (pintype "passive"))
      (node (ref "S2") (pin "1") (pinfunction "1_1") (pintype "passive"))
      (node (ref "S2") (pin "2") (pinfunction "1_2") (pintype "passive"))
      (node (ref "U1") (pin "4") (pinfunction "GND_4") (pintype "power_in"))
      (node (ref "U2") (pin "GND") (pinfunction "GND_GND") (pintype "bidirectional"))
      (node (ref "U3") (pin "2") (pinfunction "ADDR_2") (pintype "input"))
      (node (ref "U3") (pin "3") (pinfunction "GND_3") (pintype "power_in"))
      (node (ref "U4") (pin "1") (pinfunction "A0_1") (pintype "bidirectional"))
      (node (ref "U4") (pin "14") (pinfunction "GND_14") (pintype "power_in"))
      (node (ref "U4") (pin "2") (pinfunction "A1_2") (pintype "bidirectional"))
      (node (ref "U4") (pin "24") (pinfunction "A5_24") (pintype "bidirectional"))
      (node (ref "U4") (pin "25") (pinfunction "EXTCLK_25") (pintype "input"))
      (node (ref "U4") (pin "3") (pinfunction "A2_3") (pintype "bidirectional"))
      (node (ref "U4") (pin "4") (pinfunction "A3_4") (pintype "bidirectional"))
      (node (ref "U4") (pin "5") (pinfunction "A4_5") (pintype "bidirectional"))
      (node (ref "U5") (pin "2") (pinfunction "GND_2") (pintype "bidirectional"))
      (node (ref "U6") (pin "14") (pinfunction "GND_14") (pintype "power_in"))
      (node (ref "U6") (pin "2") (pinfunction "A1_2") (pintype "bidirectional"))
      (node (ref "U6") (pin "24") (pinfunction "A5_24") (pintype "bidirectional"))
      (node (ref "U6") (pin "25") (pinfunction "EXTCLK_25") (pintype "input"))
      (node (ref "U6") (pin "3") (pinfunction "A2_3") (pintype "bidirectional"))
      (node (ref "U6") (pin "4") (pinfunction "A3_4") (pintype "bidirectional"))
      (node (ref "U6") (pin "5") (pinfunction "A4_5") (pintype "bidirectional"))
      (node (ref "U7") (pin "1") (pinfunction "ADJ_1") (pintype "input"))
    )
    (net (code "5") (name "Net-(C6-+)") (class "Default")
      (node (ref "C6") (pin "VCC") (pinfunction "+_VCC") (pintype "passive"))
      (node (ref "D8") (pin "3") (pinfunction "C_3") (pintype "passive"))
      (node (ref "U1") (pin "3") (pinfunction "VBACK_3") (pintype "power_in"))
    )
    (net (code "6") (name "Net-(D1-PadA)") (class "Default")
      (node (ref "D1") (pin "A") (pinfunction "A_A") (pintype "passive"))
      (node (ref "D9") (pin "C") (pinfunction "C_C") (pintype "passive"))
    )
    (net (code "7") (name "Net-(D8-A)") (class "Default")
      (node (ref "D8") (pin "1") (pinfunction "A_1") (pintype "passive"))
      (node (ref "R1") (pin "2") (pinfunction "2_2") (pintype "passive"))
    )
    (net (code "8") (name "Net-(D10-PadA)") (class "Default")
      (node (ref "D10") (pin "A") (pinfunction "A_A") (pintype "passive"))
      (node (ref "D17") (pin "C") (pinfunction "C_C") (pintype "passive"))
    )
    (net (code "9") (name "Net-(D10-PadC)") (class "Default")
      (node (ref "D10") (pin "C") (pinfunction "C_C") (pintype "passive"))
      (node (ref "D2") (pin "A") (pinfunction "A_A") (pintype "passive"))
    )
    (net (code "10") (name "Net-(D11-PadA)") (class "Default")
      (node (ref "D11") (pin "A") (pinfunction "A_A") (pintype "passive"))
      (node (ref "D18") (pin "C") (pinfunction "C_C") (pintype "passive"))
    )
    (net (code "11") (name "Net-(D11-PadC)") (class "Default")
      (node (ref "D11") (pin "C") (pinfunction "C_C") (pintype "passive"))
      (node (ref "D3") (pin "A") (pinfunction "A_A") (pintype "passive"))
    )
    (net (code "12") (name "Net-(D12-PadA)") (class "Default")
      (node (ref "D12") (pin "A") (pinfunction "A_A") (pintype "passive"))
      (node (ref "D19") (pin "C") (pinfunction "C_C") (pintype "passive"))
    )
    (net (code "13") (name "Net-(D12-PadC)") (class "Default")
      (node (ref "D12") (pin "C") (pinfunction "C_C") (pintype "passive"))
      (node (ref "D4") (pin "A") (pinfunction "A_A") (pintype "passive"))
    )
    (net (code "14") (name "Net-(D13-PadA)") (class "Default")
      (node (ref "D13") (pin "A") (pinfunction "A_A") (pintype "passive"))
      (node (ref "D20") (pin "C") (pinfunction "C_C") (pintype "passive"))
    )
    (net (code "15") (name "Net-(D13-PadC)") (class "Default")
      (node (ref "D13") (pin "C") (pinfunction "C_C") (pintype "passive"))
      (node (ref "D5") (pin "A") (pinfunction "A_A") (pintype "passive"))
    )
    (net (code "16") (name "Net-(D14-PadA)") (class "Default")
      (node (ref "D14") (pin "A") (pinfunction "A_A") (pintype "passive"))
      (node (ref "D21") (pin "C") (pinfunction "C_C") (pintype "passive"))
    )
    (net (code "17") (name "Net-(D14-PadC)") (class "Default")
      (node (ref "D14") (pin "C") (pinfunction "C_C") (pintype "passive"))
      (node (ref "D6") (pin "A") (pinfunction "A_A") (pintype "passive"))
    )
    (net (code "18") (name "Net-(D15-PadA)") (class "Default")
      (node (ref "D15") (pin "A") (pinfunction "A_A") (pintype "passive"))
      (node (ref "D22") (pin "C") (pinfunction "C_C") (pintype "passive"))
    )
    (net (code "19") (name "Net-(D15-PadC)") (class "Default")
      (node (ref "D15") (pin "C") (pinfunction "C_C") (pintype "passive"))
      (node (ref "D7") (pin "A") (pinfunction "A_A") (pintype "passive"))
    )
    (net (code "20") (name "Net-(D16-PadA)") (class "Default")
      (node (ref "D16") (pin "A") (pinfunction "A_A") (pintype "passive"))
      (node (ref "R4") (pin "1") (pinfunction "1_1") (pintype "passive"))
    )
    (net (code "21") (name "Net-(D16-PadC)") (class "Default")
      (node (ref "D16") (pin "C") (pinfunction "C_C") (pintype "passive"))
      (node (ref "D9") (pin "A") (pinfunction "A_A") (pintype "passive"))
    )
    (net (code "22") (name "Net-(D17-PadA)") (class "Default")
      (node (ref "D17") (pin "A") (pinfunction "A_A") (pintype "passive"))
      (node (ref "R5") (pin "1") (pinfunction "1_1") (pintype "passive"))
    )
    (net (code "23") (name "Net-(D18-PadA)") (class "Default")
      (node (ref "D18") (pin "A") (pinfunction "A_A") (pintype "passive"))
      (node (ref "R6") (pin "1") (pinfunction "1_1") (pintype "passive"))
    )
    (net (code "24") (name "Net-(D19-PadA)") (class "Default")
      (node (ref "D19") (pin "A") (pinfunction "A_A") (pintype "passive"))
      (node (ref "R7") (pin "1") (pinfunction "1_1") (pintype "passive"))
    )
    (net (code "25") (name "Net-(D20-PadA)") (class "Default")
      (node (ref "D20") (pin "A") (pinfunction "A_A") (pintype "passive"))
      (node (ref "R8") (pin "1") (pinfunction "1_1") (pintype "passive"))
    )
    (net (code "26") (name "Net-(D21-PadA)") (class "Default")
      (node (ref "D21") (pin "A") (pinfunction "A_A") (pintype "passive"))
      (node (ref "R9") (pin "1") (pinfunction "1_1") (pintype "passive"))
    )
    (net (code "27") (name "Net-(D22-PadA)") (class "Default")
      (node (ref "D22") (pin "A") (pinfunction "A_A") (pintype "passive"))
      (node (ref "R10") (pin "1") (pinfunction "1_1") (pintype "passive"))
    )
    (net (code "28") (name "Net-(D23-PadA)") (class "Default")
      (node (ref "D23") (pin "A") (pinfunction "A_A") (pintype "passive"))
      (node (ref "D30") (pin "C") (pinfunction "C_C") (pintype "passive"))
    )
    (net (code "29") (name "Net-(D24-PadA)") (class "Default")
      (node (ref "D24") (pin "A") (pinfunction "A_A") (pintype "passive"))
      (node (ref "D31") (pin "C") (pinfunction "C_C") (pintype "passive"))
    )
    (net (code "30") (name "Net-(D25-PadA)") (class "Default")
      (node (ref "D25") (pin "A") (pinfunction "A_A") (pintype "passive"))
      (node (ref "D32") (pin "C") (pinfunction "C_C") (pintype "passive"))
    )
    (net (code "31") (name "Net-(D26-PadA)") (class "Default")
      (node (ref "D26") (pin "A") (pinfunction "A_A") (pintype "passive"))
      (node (ref "D33") (pin "C") (pinfunction "C_C") (pintype "passive"))
    )
    (net (code "32") (name "Net-(D27-PadA)") (class "Default")
      (node (ref "D27") (pin "A") (pinfunction "A_A") (pintype "passive"))
      (node (ref "D34") (pin "C") (pinfunction "C_C") (pintype "passive"))
    )
    (net (code "33") (name "Net-(D28-PadA)") (class "Default")
      (node (ref "D28") (pin "A") (pinfunction "A_A") (pintype "passive"))
      (node (ref "D35") (pin "C") (pinfunction "C_C") (pintype "passive"))
    )
    (net (code "34") (name "Net-(D29-PadA)") (class "Default")
      (node (ref "D29") (pin "A") (pinfunction "A_A") (pintype "passive"))
      (node (ref "D36") (pin "C") (pinfunction "C_C") (pintype "passive"))
    )
    (net (code "35") (name "Net-(D30-PadA)") (class "Default")
      (node (ref "D30") (pin "A") (pinfunction "A_A") (pintype "passive"))
      (node (ref "D37") (pin "C") (pinfunction "C_C") (pintype "passive"))
    )
    (net (code "36") (name "Net-(D31-PadA)") (class "Default")
      (node (ref "D31") (pin "A") (pinfunction "A_A") (pintype "passive"))
      (node (ref "D38") (pin "C") (pinfunction "C_C") (pintype "passive"))
    )
    (net (code "37") (name "Net-(D32-PadA)") (class "Default")
      (node (ref "D32") (pin "A") (pinfunction "A_A") (pintype "passive"))
      (node (ref "D39") (pin "C") (pinfunction "C_C") (pintype "passive"))
    )
    (net (code "38") (name "Net-(D33-PadA)") (class "Default")
      (node (ref "D33") (pin "A") (pinfunction "A_A") (pintype "passive"))
      (node (ref "D40") (pin "C") (pinfunction "C_C") (pintype "passive"))
    )
    (net (code "39") (name "Net-(D34-PadA)") (class "Default")
      (node (ref "D34") (pin "A") (pinfunction "A_A") (pintype "passive"))
      (node (ref "D41") (pin "C") (pinfunction "C_C") (pintype "passive"))
    )
    (net (code "40") (name "Net-(D35-PadA)") (class "Default")
      (node (ref "D35") (pin "A") (pinfunction "A_A") (pintype "passive"))
      (node (ref "D42") (pin "C") (pinfunction "C_C") (pintype "passive"))
    )
    (net (code "41") (name "Net-(D36-PadA)") (class "Default")
      (node (ref "D36") (pin "A") (pinfunction "A_A") (pintype "passive"))
      (node (ref "D43") (pin "C") (pinfunction "C_C") (pintype "passive"))
    )
    (net (code "42") (name "Net-(D37-PadA)") (class "Default")
      (node (ref "D37") (pin "A") (pinfunction "A_A") (pintype "passive"))
      (node (ref "R17") (pin "1") (pinfunction "1_1") (pintype "passive"))
    )
    (net (code "43") (name "Net-(D38-PadA)") (class "Default")
      (node (ref "D38") (pin "A") (pinfunction "A_A") (pintype "passive"))
      (node (ref "R18") (pin "1") (pinfunction "1_1") (pintype "passive"))
    )
    (net (code "44") (name "Net-(D39-PadA)") (class "Default")
      (node (ref "D39") (pin "A") (pinfunction "A_A") (pintype "passive"))
      (node (ref "R19") (pin "1") (pinfunction "1_1") (pintype "passive"))
    )
    (net (code "45") (name "Net-(D40-PadA)") (class "Default")
      (node (ref "D40") (pin "A") (pinfunction "A_A") (pintype "passive"))
      (node (ref "R20") (pin "1") (pinfunction "1_1") (pintype "passive"))
    )
    (net (code "46") (name "Net-(D41-PadA)") (class "Default")
      (node (ref "D41") (pin "A") (pinfunction "A_A") (pintype "passive"))
      (node (ref "R21") (pin "1") (pinfunction "1_1") (pintype "passive"))
    )
    (net (code "47") (name "Net-(D42-PadA)") (class "Default")
      (node (ref "D42") (pin "A") (pinfunction "A_A") (pintype "passive"))
      (node (ref "R22") (pin "1") (pinfunction "1_1") (pintype "passive"))
    )
    (net (code "48") (name "Net-(D43-PadA)") (class "Default")
      (node (ref "D43") (pin "A") (pinfunction "A_A") (pintype "passive"))
      (node (ref "R23") (pin "1") (pinfunction "1_1") (pintype "passive"))
    )
    (net (code "49") (name "Net-(D44-PadA)") (class "Default")
      (node (ref "D44") (pin "A") (pinfunction "A_A") (pintype "passive"))
      (node (ref "D51") (pin "C") (pinfunction "C_C") (pintype "passive"))
    )
    (net (code "50") (name "Net-(D45-PadA)") (class "Default")
      (node (ref "D45") (pin "A") (pinfunction "A_A") (pintype "passive"))
      (node (ref "D52") (pin "C") (pinfunction "C_C") (pintype "passive"))
    )
    (net (code "51") (name "Net-(D46-PadA)") (class "Default")
      (node (ref "D46") (pin "A") (pinfunction "A_A") (pintype "passive"))
      (node (ref "D53") (pin "C") (pinfunction "C_C") (pintype "passive"))
    )
    (net (code "52") (name "Net-(D47-PadA)") (class "Default")
      (node (ref "D47") (pin "A") (pinfunction "A_A") (pintype "passive"))
      (node (ref "D54") (pin "C") (pinfunction "C_C") (pintype "passive"))
    )
    (net (code "53") (name "Net-(D48-PadA)") (class "Default")
      (node (ref "D48") (pin "A") (pinfunction "A_A") (pintype "passive"))
      (node (ref "D55") (pin "C") (pinfunction "C_C") (pintype "passive"))
    )
    (net (code "54") (name "Net-(D49-PadA)") (class "Default")
      (node (ref "D49") (pin "A") (pinfunction "A_A") (pintype "passive"))
      (node (ref "D56") (pin "C") (pinfunction "C_C") (pintype "passive"))
    )
    (net (code "55") (name "Net-(D50-PadA)") (class "Default")
      (node (ref "D50") (pin "A") (pinfunction "A_A") (pintype "passive"))
      (node (ref "D57") (pin "C") (pinfunction "C_C") (pintype "passive"))
    )
    (net (code "56") (name "Net-(D51-PadA)") (class "Default")
      (node (ref "D51") (pin "A") (pinfunction "A_A") (pintype "passive"))
      (node (ref "D58") (pin "C") (pinfunction "C_C") (pintype "passive"))
    )
    (net (code "57") (name "Net-(D52-PadA)") (class "Default")
      (node (ref "D52") (pin "A") (pinfunction "A_A") (pintype "passive"))
      (node (ref "D59") (pin "C") (pinfunction "C_C") (pintype "passive"))
    )
    (net (code "58") (name "Net-(D53-PadA)") (class "Default")
      (node (ref "D53") (pin "A") (pinfunction "A_A") (pintype "passive"))
      (node (ref "D60") (pin "C") (pinfunction "C_C") (pintype "passive"))
    )
    (net (code "59") (name "Net-(D54-PadA)") (class "Default")
      (node (ref "D54") (pin "A") (pinfunction "A_A") (pintype "passive"))
      (node (ref "D61") (pin "C") (pinfunction "C_C") (pintype "passive"))
    )
    (net (code "60") (name "Net-(D55-PadA)") (class "Default")
      (node (ref "D55") (pin "A") (pinfunction "A_A") (pintype "passive"))
      (node (ref "D62") (pin "C") (pinfunction "C_C") (pintype "passive"))
    )
    (net (code "61") (name "Net-(D56-PadA)") (class "Default")
      (node (ref "D56") (pin "A") (pinfunction "A_A") (pintype "passive"))
      (node (ref "D63") (pin "C") (pinfunction "C_C") (pintype "passive"))
    )
    (net (code "62") (name "Net-(D57-PadA)") (class "Default")
      (node (ref "D57") (pin "A") (pinfunction "A_A") (pintype "passive"))
      (node (ref "D64") (pin "C") (pinfunction "C_C") (pintype "passive"))
    )
    (net (code "63") (name "Net-(D58-PadA)") (class "Default")
      (node (ref "D58") (pin "A") (pinfunction "A_A") (pintype "passive"))
      (node (ref "R25") (pin "1") (pinfunction "1_1") (pintype "passive"))
    )
    (net (code "64") (name "Net-(D59-PadA)") (class "Default")
      (node (ref "D59") (pin "A") (pinfunction "A_A") (pintype "passive"))
      (node (ref "R26") (pin "1") (pinfunction "1_1") (pintype "passive"))
    )
    (net (code "65") (name "Net-(D60-PadA)") (class "Default")
      (node (ref "D60") (pin "A") (pinfunction "A_A") (pintype "passive"))
      (node (ref "R27") (pin "1") (pinfunction "1_1") (pintype "passive"))
    )
    (net (code "66") (name "Net-(D61-PadA)") (class "Default")
      (node (ref "D61") (pin "A") (pinfunction "A_A") (pintype "passive"))
      (node (ref "R28") (pin "1") (pinfunction "1_1") (pintype "passive"))
    )
    (net (code "67") (name "Net-(D62-PadA)") (class "Default")
      (node (ref "D62") (pin "A") (pinfunction "A_A") (pintype "passive"))
      (node (ref "R29") (pin "1") (pinfunction "1_1") (pintype "passive"))
    )
    (net (code "68") (name "Net-(D63-PadA)") (class "Default")
      (node (ref "D63") (pin "A") (pinfunction "A_A") (pintype "passive"))
      (node (ref "R30") (pin "1") (pinfunction "1_1") (pintype "passive"))
    )
    (net (code "69") (name "Net-(D64-PadA)") (class "Default")
      (node (ref "D64") (pin "A") (pinfunction "A_A") (pintype "passive"))
      (node (ref "R31") (pin "1") (pinfunction "1_1") (pintype "passive"))
    )
    (net (code "70") (name "Net-(D65-PadA)") (class "Default")
      (node (ref "D65") (pin "A") (pinfunction "A_A") (pintype "passive"))
      (node (ref "D72") (pin "C") (pinfunction "C_C") (pintype "passive"))
    )
    (net (code "71") (name "Net-(D66-PadA)") (class "Default")
      (node (ref "D66") (pin "A") (pinfunction "A_A") (pintype "passive"))
      (node (ref "D73") (pin "C") (pinfunction "C_C") (pintype "passive"))
    )
    (net (code "72") (name "Net-(D67-PadA)") (class "Default")
      (node (ref "D67") (pin "A") (pinfunction "A_A") (pintype "passive"))
      (node (ref "D74") (pin "C") (pinfunction "C_C") (pintype "passive"))
    )
    (net (code "73") (name "Net-(D68-PadA)") (class "Default")
      (node (ref "D68") (pin "A") (pinfunction "A_A") (pintype "passive"))
      (node (ref "D75") (pin "C") (pinfunction "C_C") (pintype "passive"))
    )
    (net (code "74") (name "Net-(D69-PadA)") (class "Default")
      (node (ref "D69") (pin "A") (pinfunction "A_A") (pintype "passive"))
      (node (ref "D76") (pin "C") (pinfunction "C_C") (pintype "passive"))
    )
    (net (code "75") (name "Net-(D70-PadA)") (class "Default")
      (node (ref "D70") (pin "A") (pinfunction "A_A") (pintype "passive"))
      (node (ref "D77") (pin "C") (pinfunction "C_C") (pintype "passive"))
    )
    (net (code "76") (name "Net-(D71-PadA)") (class "Default")
      (node (ref "D71") (pin "A") (pinfunction "A_A") (pintype "passive"))
      (node (ref "D78") (pin "C") (pinfunction "C_C") (pintype "passive"))
    )
    (net (code "77") (name "Net-(D72-PadA)") (class "Default")
      (node (ref "D72") (pin "A") (pinfunction "A_A") (pintype "passive"))
      (node (ref "D79") (pin "C") (pinfunction "C_C") (pintype "passive"))
    )
    (net (code "78") (name "Net-(D73-PadA)") (class "Default")
      (node (ref "D73") (pin "A") (pinfunction "A_A") (pintype "passive"))
      (node (ref "D80") (pin "C") (pinfunction "C_C") (pintype "passive"))
    )
    (net (code "79") (name "Net-(D74-PadA)") (class "Default")
      (node (ref "D74") (pin "A") (pinfunction "A_A") (pintype "passive"))
      (node (ref "D81") (pin "C") (pinfunction "C_C") (pintype "passive"))
    )
    (net (code "80") (name "Net-(D75-PadA)") (class "Default")
      (node (ref "D75") (pin "A") (pinfunction "A_A") (pintype "passive"))
      (node (ref "D82") (pin "C") (pinfunction "C_C") (pintype "passive"))
    )
    (net (code "81") (name "Net-(D76-PadA)") (class "Default")
      (node (ref "D76") (pin "A") (pinfunction "A_A") (pintype "passive"))
      (node (ref "D83") (pin "C") (pinfunction "C_C") (pintype "passive"))
    )
    (net (code "82") (name "Net-(D77-PadA)") (class "Default")
      (node (ref "D77") (pin "A") (pinfunction "A_A") (pintype "passive"))
      (node (ref "D84") (pin "C") (pinfunction "C_C") (pintype "passive"))
    )
    (net (code "83") (name "Net-(D78-PadA)") (class "Default")
      (node (ref "D78") (pin "A") (pinfunction "A_A") (pintype "passive"))
      (node (ref "D85") (pin "C") (pinfunction "C_C") (pintype "passive"))
    )
    (net (code "84") (name "Net-(D79-PadA)") (class "Default")
      (node (ref "D79") (pin "A") (pinfunction "A_A") (pintype "passive"))
      (node (ref "R34") (pin "1") (pinfunction "1_1") (pintype "passive"))
    )
    (net (code "85") (name "Net-(D80-PadA)") (class "Default")
      (node (ref "D80") (pin "A") (pinfunction "A_A") (pintype "passive"))
      (node (ref "R35") (pin "1") (pinfunction "1_1") (pintype "passive"))
    )
    (net (code "86") (name "Net-(D81-PadA)") (class "Default")
      (node (ref "D81") (pin "A") (pinfunction "A_A") (pintype "passive"))
      (node (ref "R36") (pin "1") (pinfunction "1_1") (pintype "passive"))
    )
    (net (code "87") (name "Net-(D82-PadA)") (class "Default")
      (node (ref "D82") (pin "A") (pinfunction "A_A") (pintype "passive"))
      (node (ref "R37") (pin "1") (pinfunction "1_1") (pintype "passive"))
    )
    (net (code "88") (name "Net-(D83-PadA)") (class "Default")
      (node (ref "D83") (pin "A") (pinfunction "A_A") (pintype "passive"))
      (node (ref "R38") (pin "1") (pinfunction "1_1") (pintype "passive"))
    )
    (net (code "89") (name "Net-(D84-PadA)") (class "Default")
      (node (ref "D84") (pin "A") (pinfunction "A_A") (pintype "passive"))
      (node (ref "R39") (pin "1") (pinfunction "1_1") (pintype "passive"))
    )
    (net (code "90") (name "Net-(D85-PadA)") (class "Default")
      (node (ref "D85") (pin "A") (pinfunction "A_A") (pintype "passive"))
      (node (ref "R40") (pin "1") (pinfunction "1_1") (pintype "passive"))
    )
    (net (code "91") (name "Net-(D86-PadA)") (class "Default")
      (node (ref "D86") (pin "A") (pinfunction "A_A") (pintype "passive"))
      (node (ref "D87") (pin "C") (pinfunction "C_C") (pintype "passive"))
    )
    (net (code "92") (name "Net-(D87-PadA)") (class "Default")
      (node (ref "D87") (pin "A") (pinfunction "A_A") (pintype "passive"))
      (node (ref "R41") (pin "1") (pinfunction "1_1") (pintype "passive"))
    )
    (net (code "93") (name "Net-(D88-PadA)") (class "Default")
      (node (ref "D88") (pin "A") (pinfunction "A_A") (pintype "passive"))
      (node (ref "R42") (pin "1") (pinfunction "1_1") (pintype "passive"))
    )
    (net (code "94") (name "Net-(Q1-D)") (class "Default")
      (node (ref "D1") (pin "C") (pinfunction "C_C") (pintype "passive"))
      (node (ref "Q1") (pin "3") (pinfunction "D_3") (pintype "passive"))
    )
    (net (code "95") (name "Net-(Q2-D)") (class "Default")
      (node (ref "D2") (pin "C") (pinfunction "C_C") (pintype "passive"))
      (node (ref "Q2") (pin "3") (pinfunction "D_3") (pintype "passive"))
    )
    (net (code "96") (name "Net-(Q3-D)") (class "Default")
      (node (ref "D3") (pin "C") (pinfunction "C_C") (pintype "passive"))
      (node (ref "Q3") (pin "3") (pinfunction "D_3") (pintype "passive"))
    )
    (net (code "97") (name "Net-(Q4-D)") (class "Default")
      (node (ref "D4") (pin "C") (pinfunction "C_C") (pintype "passive"))
      (node (ref "Q4") (pin "3") (pinfunction "D_3") (pintype "passive"))
    )
    (net (code "98") (name "Net-(Q5-D)") (class "Default")
      (node (ref "D5") (pin "C") (pinfunction "C_C") (pintype "passive"))
      (node (ref "Q5") (pin "3") (pinfunction "D_3") (pintype "passive"))
    )
    (net (code "99") (name "Net-(Q6-D)") (class "Default")
      (node (ref "D6") (pin "C") (pinfunction "C_C") (pintype "passive"))
      (node (ref "Q6") (pin "3") (pinfunction "D_3") (pintype "passive"))
    )
    (net (code "100") (name "Net-(Q7-D)") (class "Default")
      (node (ref "D7") (pin "C") (pinfunction "C_C") (pintype "passive"))
      (node (ref "Q7") (pin "3") (pinfunction "D_3") (pintype "passive"))
    )
    (net (code "101") (name "Net-(Q8-D)") (class "Default")
      (node (ref "D23") (pin "C") (pinfunction "C_C") (pintype "passive"))
      (node (ref "Q8") (pin "3") (pinfunction "D_3") (pintype "passive"))
    )
    (net (code "102") (name "Net-(Q9-D)") (class "Default")
      (node (ref "D24") (pin "C") (pinfunction "C_C") (pintype "passive"))
      (node (ref "Q9") (pin "3") (pinfunction "D_3") (pintype "passive"))
    )
    (net (code "103") (name "Net-(Q10-D)") (class "Default")
      (node (ref "D25") (pin "C") (pinfunction "C_C") (pintype "passive"))
      (node (ref "Q10") (pin "3") (pinfunction "D_3") (pintype "passive"))
    )
    (net (code "104") (name "Net-(Q11-D)") (class "Default")
      (node (ref "D26") (pin "C") (pinfunction "C_C") (pintype "passive"))
      (node (ref "Q11") (pin "3") (pinfunction "D_3") (pintype "passive"))
    )
    (net (code "105") (name "Net-(Q12-D)") (class "Default")
      (node (ref "D27") (pin "C") (pinfunction "C_C") (pintype "passive"))
      (node (ref "Q12") (pin "3") (pinfunction "D_3") (pintype "passive"))
    )
    (net (code "106") (name "Net-(Q13-D)") (class "Default")
      (node (ref "D28") (pin "C") (pinfunction "C_C") (pintype "passive"))
      (node (ref "Q13") (pin "3") (pinfunction "D_3") (pintype "passive"))
    )
    (net (code "107") (name "Net-(Q14-D)") (class "Default")
      (node (ref "D29") (pin "C") (pinfunction "C_C") (pintype "passive"))
      (node (ref "Q14") (pin "3") (pinfunction "D_3") (pintype "passive"))
    )
    (net (code "108") (name "Net-(Q15-D)") (class "Default")
      (node (ref "D44") (pin "C") (pinfunction "C_C") (pintype "passive"))
      (node (ref "Q15") (pin "3") (pinfunction "D_3") (pintype "passive"))
    )
    (net (code "109") (name "Net-(Q16-D)") (class "Default")
      (node (ref "D45") (pin "C") (pinfunction "C_C") (pintype "passive"))
      (node (ref "Q16") (pin "3") (pinfunction "D_3") (pintype "passive"))
    )
    (net (code "110") (name "Net-(Q17-D)") (class "Default")
      (node (ref "D46") (pin "C") (pinfunction "C_C") (pintype "passive"))
      (node (ref "Q17") (pin "3") (pinfunction "D_3") (pintype "passive"))
    )
    (net (code "111") (name "Net-(Q18-D)") (class "Default")
      (node (ref "D47") (pin "C") (pinfunction "C_C") (pintype "passive"))
      (node (ref "Q18") (pin "3") (pinfunction "D_3") (pintype "passive"))
    )
    (net (code "112") (name "Net-(Q19-D)") (class "Default")
      (node (ref "D48") (pin "C") (pinfunction "C_C") (pintype "passive"))
      (node (ref "Q19") (pin "3") (pinfunction "D_3") (pintype "passive"))
    )
    (net (code "113") (name "Net-(Q20-D)") (class "Default")
      (node (ref "D49") (pin "C") (pinfunction "C_C") (pintype "passive"))
      (node (ref "Q20") (pin "3") (pinfunction "D_3") (pintype "passive"))
    )
    (net (code "114") (name "Net-(Q21-D)") (class "Default")
      (node (ref "D50") (pin "C") (pinfunction "C_C") (pintype "passive"))
      (node (ref "Q21") (pin "3") (pinfunction "D_3") (pintype "passive"))
    )
    (net (code "115") (name "Net-(Q22-D)") (class "Default")
      (node (ref "D65") (pin "C") (pinfunction "C_C") (pintype "passive"))
      (node (ref "Q22") (pin "3") (pinfunction "D_3") (pintype "passive"))
    )
    (net (code "116") (name "Net-(Q23-D)") (class "Default")
      (node (ref "D66") (pin "C") (pinfunction "C_C") (pintype "passive"))
      (node (ref "Q23") (pin "3") (pinfunction "D_3") (pintype "passive"))
    )
    (net (code "117") (name "Net-(Q24-D)") (class "Default")
      (node (ref "D67") (pin "C") (pinfunction "C_C") (pintype "passive"))
      (node (ref "Q24") (pin "3") (pinfunction "D_3") (pintype "passive"))
    )
    (net (code "118") (name "Net-(Q25-D)") (class "Default")
      (node (ref "D68") (pin "C") (pinfunction "C_C") (pintype "passive"))
      (node (ref "Q25") (pin "3") (pinfunction "D_3") (pintype "passive"))
    )
    (net (code "119") (name "Net-(Q26-D)") (class "Default")
      (node (ref "D69") (pin "C") (pinfunction "C_C") (pintype "passive"))
      (node (ref "Q26") (pin "3") (pinfunction "D_3") (pintype "passive"))
    )
    (net (code "120") (name "Net-(Q27-D)") (class "Default")
      (node (ref "D70") (pin "C") (pinfunction "C_C") (pintype "passive"))
      (node (ref "Q27") (pin "3") (pinfunction "D_3") (pintype "passive"))
    )
    (net (code "121") (name "Net-(Q28-D)") (class "Default")
      (node (ref "D71") (pin "C") (pinfunction "C_C") (pintype "passive"))
      (node (ref "Q28") (pin "3") (pinfunction "D_3") (pintype "passive"))
    )
    (net (code "122") (name "Net-(Q29-D)") (class "Default")
      (node (ref "D86") (pin "C") (pinfunction "C_C") (pintype "passive"))
      (node (ref "Q29") (pin "3") (pinfunction "D_3") (pintype "passive"))
    )
    (net (code "123") (name "Net-(Q30-D)") (class "Default")
      (node (ref "D88") (pin "C") (pinfunction "C_C") (pintype "passive"))
      (node (ref "Q30") (pin "3") (pinfunction "D_3") (pintype "passive"))
    )
    (net (code "124") (name "Net-(R2-Pad1)") (class "Default")
      (node (ref "R2") (pin "1") (pinfunction "1_1") (pintype "passive"))
      (node (ref "U2") (pin "CH_PD") (pinfunction "CH_PD_CH_PD") (pintype "bidirectional"))
    )
    (net (code "125") (name "Net-(R11-Pad2)") (class "Default")
      (node (ref "R11") (pin "2") (pinfunction "2_2") (pintype "passive"))
      (node (ref "U2") (pin "GPIO15") (pinfunction "GPIO15_GPIO15") (pintype "bidirectional"))
    )
    (net (code "126") (name "Net-(R15-Pad1)") (class "Default")
      (node (ref "R15") (pin "1") (pinfunction "1_1") (pintype "passive"))
      (node (ref "S2") (pin "3") (pinfunction "2_3") (pintype "passive"))
      (node (ref "S2") (pin "4") (pinfunction "2_4") (pintype "passive"))
      (node (ref "U2") (pin "GPIO0") (pinfunction "GPIO0_GPIO0") (pintype "bidirectional"))
    )
    (net (code "127") (name "Net-(R16-Pad1)") (class "Default")
      (node (ref "R16") (pin "1") (pinfunction "1_1") (pintype "passive"))
      (node (ref "U2") (pin "GPIO2") (pinfunction "GPIO2_GPIO2") (pintype "bidirectional"))
    )
    (net (code "128") (name "Net-(U1-X1)") (class "Default")
      (node (ref "U1") (pin "1") (pinfunction "X1_1") (pintype "bidirectional"))
      (node (ref "Y1") (pin "2") (pinfunction "2_2") (pintype "passive"))
    )
    (net (code "129") (name "Net-(U1-X2)") (class "Default")
      (node (ref "U1") (pin "2") (pinfunction "X2_2") (pintype "bidirectional"))
      (node (ref "Y1") (pin "1") (pinfunction "1_1") (pintype "passive"))
    )
    (net (code "130") (name "Net-(U3-DVI)") (class "Default")
      (node (ref "C7") (pin "2") (pinfunction "2_2") (pintype "passive"))
      (node (ref "R14") (pin "1") (pinfunction "1_1") (pintype "passive"))
      (node (ref "U3") (pin "5") (pinfunction "DVI_5") (pintype "input"))
    )
    (net (code "131") (name "Net-(U5-BS)") (class "Default")
      (node (ref "C10") (pin "1") (pinfunction "1_1") (pintype "passive"))
      (node (ref "U5") (pin "1") (pinfunction "BS_1") (pintype "bidirectional"))
    )
    (net (code "132") (name "Net-(U5-EN)") (class "Default")
      (node (ref "R24") (pin "1") (pinfunction "1_1") (pintype "passive"))
      (node (ref "U5") (pin "4") (pinfunction "EN_4") (pintype "bidirectional"))
    )
    (net (code "133") (name "Net-(U5-FB)") (class "Default")
      (node (ref "C11") (pin "2") (pinfunction "2_2") (pintype "passive"))
      (node (ref "R32") (pin "1") (pinfunction "1_1") (pintype "passive"))
      (node (ref "R33") (pin "2") (pinfunction "2_2") (pintype "passive"))
      (node (ref "U5") (pin "3") (pinfunction "FB_3") (pintype "bidirectional"))
    )
    (net (code "134") (name "Net-(U5-SW)") (class "Default")
      (node (ref "C10") (pin "2") (pinfunction "2_2") (pintype "passive"))
      (node (ref "L1") (pin "1") (pinfunction "1_1") (pintype "passive"))
      (node (ref "U5") (pin "6") (pinfunction "SW_6") (pintype "bidirectional"))
    )
    (net (code "135") (name "Net-(U7-IN)") (class "Default")
      (node (ref "C11") (pin "1") (pinfunction "1_1") (pintype "passive"))
      (node (ref "C12") (pin "1") (pinfunction "1_1") (pintype "passive"))
      (node (ref "C13") (pin "1") (pinfunction "1_1") (pintype "passive"))
      (node (ref "L1") (pin "2") (pinfunction "2_2") (pintype "passive"))
      (node (ref "R32") (pin "2") (pinfunction "2_2") (pintype "passive"))
      (node (ref "U7") (pin "3") (pinfunction "IN_3") (pintype "input"))
    )
    (net (code "136") (name "OE") (class "Default")
      (node (ref "U2") (pin "GPIO12") (pinfunction "GPIO12_GPIO12") (pintype "bidirectional"))
      (node (ref "U4") (pin "23") (pinfunction "/OE_23") (pintype "bidirectional"))
      (node (ref "U6") (pin "23") (pinfunction "/OE_23") (pintype "bidirectional"))
    )
    (net (code "137") (name "POINT") (class "Default")
      (node (ref "Q30") (pin "1") (pinfunction "G_1") (pintype "passive"))
      (node (ref "U4") (pin "22") (pinfunction "LED15_22") (pintype "bidirectional"))
    )
    (net (code "138") (name "RST") (class "Default")
      (node (ref "J2") (pin "4") (pinfunction "4_4") (pintype "passive"))
      (node (ref "R3") (pin "1") (pinfunction "1_1") (pintype "passive"))
      (node (ref "S1") (pin "3") (pinfunction "2_3") (pintype "passive"))
      (node (ref "S1") (pin "4") (pinfunction "2_4") (pintype "passive"))
      (node (ref "U2") (pin "RESET") (pinfunction "RESET_RESET") (pintype "bidirectional"))
    )
    (net (code "139") (name "RX") (class "Default")
      (node (ref "J2") (pin "3") (pinfunction "3_3") (pintype "passive"))
      (node (ref "U2") (pin "RXD0") (pinfunction "RX_RXD0") (pintype "bidirectional"))
    )
    (net (code "140") (name "S1A") (class "Default")
      (node (ref "Q28") (pin "1") (pinfunction "G_1") (pintype "passive"))
      (node (ref "U4") (pin "6") (pinfunction "LED0_6") (pintype "bidirectional"))
    )
    (net (code "141") (name "S1B") (class "Default")
      (node (ref "Q27") (pin "1") (pinfunction "G_1") (pintype "passive"))
      (node (ref "U4") (pin "7") (pinfunction "LED1_7") (pintype "bidirectional"))
    )
    (net (code "142") (name "S1C") (class "Default")
      (node (ref "Q24") (pin "1") (pinfunction "G_1") (pintype "passive"))
      (node (ref "U4") (pin "8") (pinfunction "LED2_8") (pintype "bidirectional"))
    )
    (net (code "143") (name "S1D") (class "Default")
      (node (ref "Q22") (pin "1") (pinfunction "G_1") (pintype "passive"))
      (node (ref "U4") (pin "9") (pinfunction "LED3_9") (pintype "bidirectional"))
    )
    (net (code "144") (name "S1E") (class "Default")
      (node (ref "Q23") (pin "1") (pinfunction "G_1") (pintype "passive"))
      (node (ref "U4") (pin "10") (pinfunction "LED4_10") (pintype "bidirectional"))
    )
    (net (code "145") (name "S1F") (class "Default")
      (node (ref "Q26") (pin "1") (pinfunction "G_1") (pintype "passive"))
      (node (ref "U4") (pin "11") (pinfunction "LED5_11") (pintype "bidirectional"))
    )
    (net (code "146") (name "S1G") (class "Default")
      (node (ref "Q25") (pin "1") (pinfunction "G_1") (pintype "passive"))
      (node (ref "U4") (pin "12") (pinfunction "LED6_12") (pintype "bidirectional"))
    )
    (net (code "147") (name "S2A") (class "Default")
      (node (ref "Q21") (pin "1") (pinfunction "G_1") (pintype "passive"))
      (node (ref "U4") (pin "15") (pinfunction "LED8_15") (pintype "bidirectional"))
    )
    (net (code "148") (name "S2B") (class "Default")
      (node (ref "Q20") (pin "1") (pinfunction "G_1") (pintype "passive"))
      (node (ref "U4") (pin "16") (pinfunction "LED9_16") (pintype "bidirectional"))
    )
    (net (code "149") (name "S2C") (class "Default")
      (node (ref "Q17") (pin "1") (pinfunction "G_1") (pintype "passive"))
      (node (ref "U4") (pin "17") (pinfunction "LED10_17") (pintype "bidirectional"))
    )
    (net (code "150") (name "S2D") (class "Default")
      (node (ref "Q15") (pin "1") (pinfunction "G_1") (pintype "passive"))
      (node (ref "U4") (pin "18") (pinfunction "LED11_18") (pintype "bidirectional"))
    )
    (net (code "151") (name "S2E") (class "Default")
      (node (ref "Q16") (pin "1") (pinfunction "G_1") (pintype "passive"))
      (node (ref "U4") (pin "19") (pinfunction "LED12_19") (pintype "bidirectional"))
    )
    (net (code "152") (name "S2F") (class "Default")
      (node (ref "Q19") (pin "1") (pinfunction "G_1") (pintype "passive"))
      (node (ref "U4") (pin "20") (pinfunction "LED13_20") (pintype "bidirectional"))
    )
    (net (code "153") (name "S2G") (class "Default")
      (node (ref "Q18") (pin "1") (pinfunction "G_1") (pintype "passive"))
      (node (ref "U4") (pin "21") (pinfunction "LED14_21") (pintype "bidirectional"))
    )
    (net (code "154") (name "S3A") (class "Default")
      (node (ref "Q14") (pin "1") (pinfunction "G_1") (pintype "passive"))
      (node (ref "U6") (pin "6") (pinfunction "LED0_6") (pintype "bidirectional"))
    )
    (net (code "155") (name "S3B") (class "Default")
      (node (ref "Q13") (pin "1") (pinfunction "G_1") (pintype "passive"))
      (node (ref "U6") (pin "7") (pinfunction "LED1_7") (pintype "bidirectional"))
    )
    (net (code "156") (name "S3C") (class "Default")
      (node (ref "Q10") (pin "1") (pinfunction "G_1") (pintype "passive"))
      (node (ref "U6") (pin "8") (pinfunction "LED2_8") (pintype "bidirectional"))
    )
    (net (code "157") (name "S3D") (class "Default")
      (node (ref "Q8") (pin "1") (pinfunction "G_1") (pintype "passive"))
      (node (ref "U6") (pin "9") (pinfunction "LED3_9") (pintype "bidirectional"))
    )
    (net (code "158") (name "S3E") (class "Default")
      (node (ref "Q9") (pin "1") (pinfunction "G_1") (pintype "passive"))
      (node (ref "U6") (pin "10") (pinfunction "LED4_10") (pintype "bidirectional"))
    )
    (net (code "159") (name "S3F") (class "Default")
      (node (ref "Q12") (pin "1") (pinfunction "G_1") (pintype "passive"))
      (node (ref "U6") (pin "11") (pinfunction "LED5_11") (pintype "bidirectional"))
    )
    (net (code "160") (name "S3G") (class "Default")
      (node (ref "Q11") (pin "1") (pinfunction "G_1") (pintype "passive"))
      (node (ref "U6") (pin "12") (pinfunction "LED6_12") (pintype "bidirectional"))
    )
    (net (code "161") (name "S4A") (class "Default")
      (node (ref "Q7") (pin "1") (pinfunction "G_1") (pintype "passive"))
      (node (ref "U6") (pin "15") (pinfunction "LED8_15") (pintype "bidirectional"))
    )
    (net (code "162") (name "S4B") (class "Default")
      (node (ref "Q6") (pin "1") (pinfunction "G_1") (pintype "passive"))
      (node (ref "U6") (pin "16") (pinfunction "LED9_16") (pintype "bidirectional"))
    )
    (net (code "163") (name "S4C") (class "Default")
      (node (ref "Q3") (pin "1") (pinfunction "G_1") (pintype "passive"))
      (node (ref "U6") (pin "17") (pinfunction "LED10_17") (pintype "bidirectional"))
    )
    (net (code "164") (name "S4D") (class "Default")
      (node (ref "Q1") (pin "1") (pinfunction "G_1") (pintype "passive"))
      (node (ref "U6") (pin "18") (pinfunction "LED11_18") (pintype "bidirectional"))
    )
    (net (code "165") (name "S4E") (class "Default")
      (node (ref "Q2") (pin "1") (pinfunction "G_1") (pintype "passive"))
      (node (ref "U6") (pin "19") (pinfunction "LED12_19") (pintype "bidirectional"))
    )
    (net (code "166") (name "S4F") (class "Default")
      (node (ref "Q5") (pin "1") (pinfunction "G_1") (pintype "passive"))
      (node (ref "U6") (pin "20") (pinfunction "LED13_20") (pintype "bidirectional"))
    )
    (net (code "167") (name "S4G") (class "Default")
      (node (ref "Q4") (pin "1") (pinfunction "G_1") (pintype "passive"))
      (node (ref "U6") (pin "21") (pinfunction "LED14_21") (pintype "bidirectional"))
    )
    (net (code "168") (name "SCL") (class "Default")
      (node (ref "R12") (pin "1") (pinfunction "1_1") (pintype "passive"))
      (node (ref "U1") (pin "6") (pinfunction "SCL_6") (pintype "bidirectional"))
      (node (ref "U2") (pin "GPIO5") (pinfunction "GPIO5_GPIO5") (pintype "bidirectional"))
      (node (ref "U3") (pin "6") (pinfunction "SCL_6") (pintype "input"))
      (node (ref "U4") (pin "26") (pinfunction "SCL_26") (pintype "bidirectional"))
      (node (ref "U6") (pin "26") (pinfunction "SCL_26") (pintype "bidirectional"))
    )
    (net (code "169") (name "SDA") (class "Default")
      (node (ref "R13") (pin "1") (pinfunction "1_1") (pintype "passive"))
      (node (ref "U1") (pin "5") (pinfunction "SDA_5") (pintype "bidirectional"))
      (node (ref "U2") (pin "GPIO4") (pinfunction "GPIO4_GPIO4") (pintype "bidirectional"))
      (node (ref "U3") (pin "4") (pinfunction "SDA_4") (pintype "bidirectional"))
      (node (ref "U4") (pin "27") (pinfunction "SDA_27") (pintype "bidirectional"))
      (node (ref "U6") (pin "27") (pinfunction "SDA_27") (pintype "bidirectional"))
    )
    (net (code "170") (name "TINT") (class "Default")
      (node (ref "U1") (pin "7") (pinfunction "SQW/INT_7") (pintype "bidirectional"))
      (node (ref "U2") (pin "GPIO14") (pinfunction "GPIO14_GPIO14") (pintype "bidirectional"))
    )
    (net (code "171") (name "TX") (class "Default")
      (node (ref "J2") (pin "2") (pinfunction "2_2") (pintype "passive"))
      (node (ref "U2") (pin "TXD0") (pinfunction "TX_TXD0") (pintype "bidirectional"))
    )
    (net (code "172") (name "unconnected-(U2-*GPIO9-PadGPIO9)") (class "Default")
      (node (ref "U2") (pin "GPIO9") (pinfunction "*GPIO9_GPIO9") (pintype "bidirectional"))
    )
    (net (code "173") (name "unconnected-(U2-*GPIO10-PadGPIO10)") (class "Default")
      (node (ref "U2") (pin "GPIO10") (pinfunction "*GPIO10_GPIO10") (pintype "bidirectional"))
    )
    (net (code "174") (name "unconnected-(U2-PadADC)") (class "Default")
      (node (ref "U2") (pin "ADC") (pinfunction "ADC_ADC") (pintype "bidirectional"))
    )
    (net (code "175") (name "unconnected-(U2-PadCS0)") (class "Default")
      (node (ref "U2") (pin "CS0") (pinfunction "CS0_CS0") (pintype "bidirectional"))
    )
    (net (code "176") (name "unconnected-(U2-PadGPIO13)") (class "Default")
      (node (ref "U2") (pin "GPIO13") (pinfunction "GPIO13_GPIO13") (pintype "bidirectional"))
    )
    (net (code "177") (name "unconnected-(U2-PadGPIO16)") (class "Default")
      (node (ref "U2") (pin "GPIO16") (pinfunction "GPIO16_GPIO16") (pintype "bidirectional"))
    )
    (net (code "178") (name "unconnected-(U2-PadMISO)") (class "Default")
      (node (ref "U2") (pin "MISO") (pinfunction "MISO_MISO") (pintype "bidirectional"))
    )
    (net (code "179") (name "unconnected-(U2-PadMOSI)") (class "Default")
      (node (ref "U2") (pin "MOSI") (pinfunction "MOSI_MOSI") (pintype "bidirectional"))
    )
    (net (code "180") (name "unconnected-(U2-PadSCLK)") (class "Default")
      (node (ref "U2") (pin "SCLK") (pinfunction "SCLK_SCLK") (pintype "bidirectional"))
    )
    (net (code "181") (name "unconnected-(U4-LED7-Pad13)") (class "Default")
      (node (ref "U4") (pin "13") (pinfunction "LED7_13") (pintype "bidirectional"))
    )
    (net (code "182") (name "unconnected-(U6-LED7-Pad13)") (class "Default")
      (node (ref "U6") (pin "13") (pinfunction "LED7_13") (pintype "bidirectional"))
    )
  )
)
